# EC01_esquematico_easyeda.net
KiCad netlist of a schematic drawn in EasyEDA
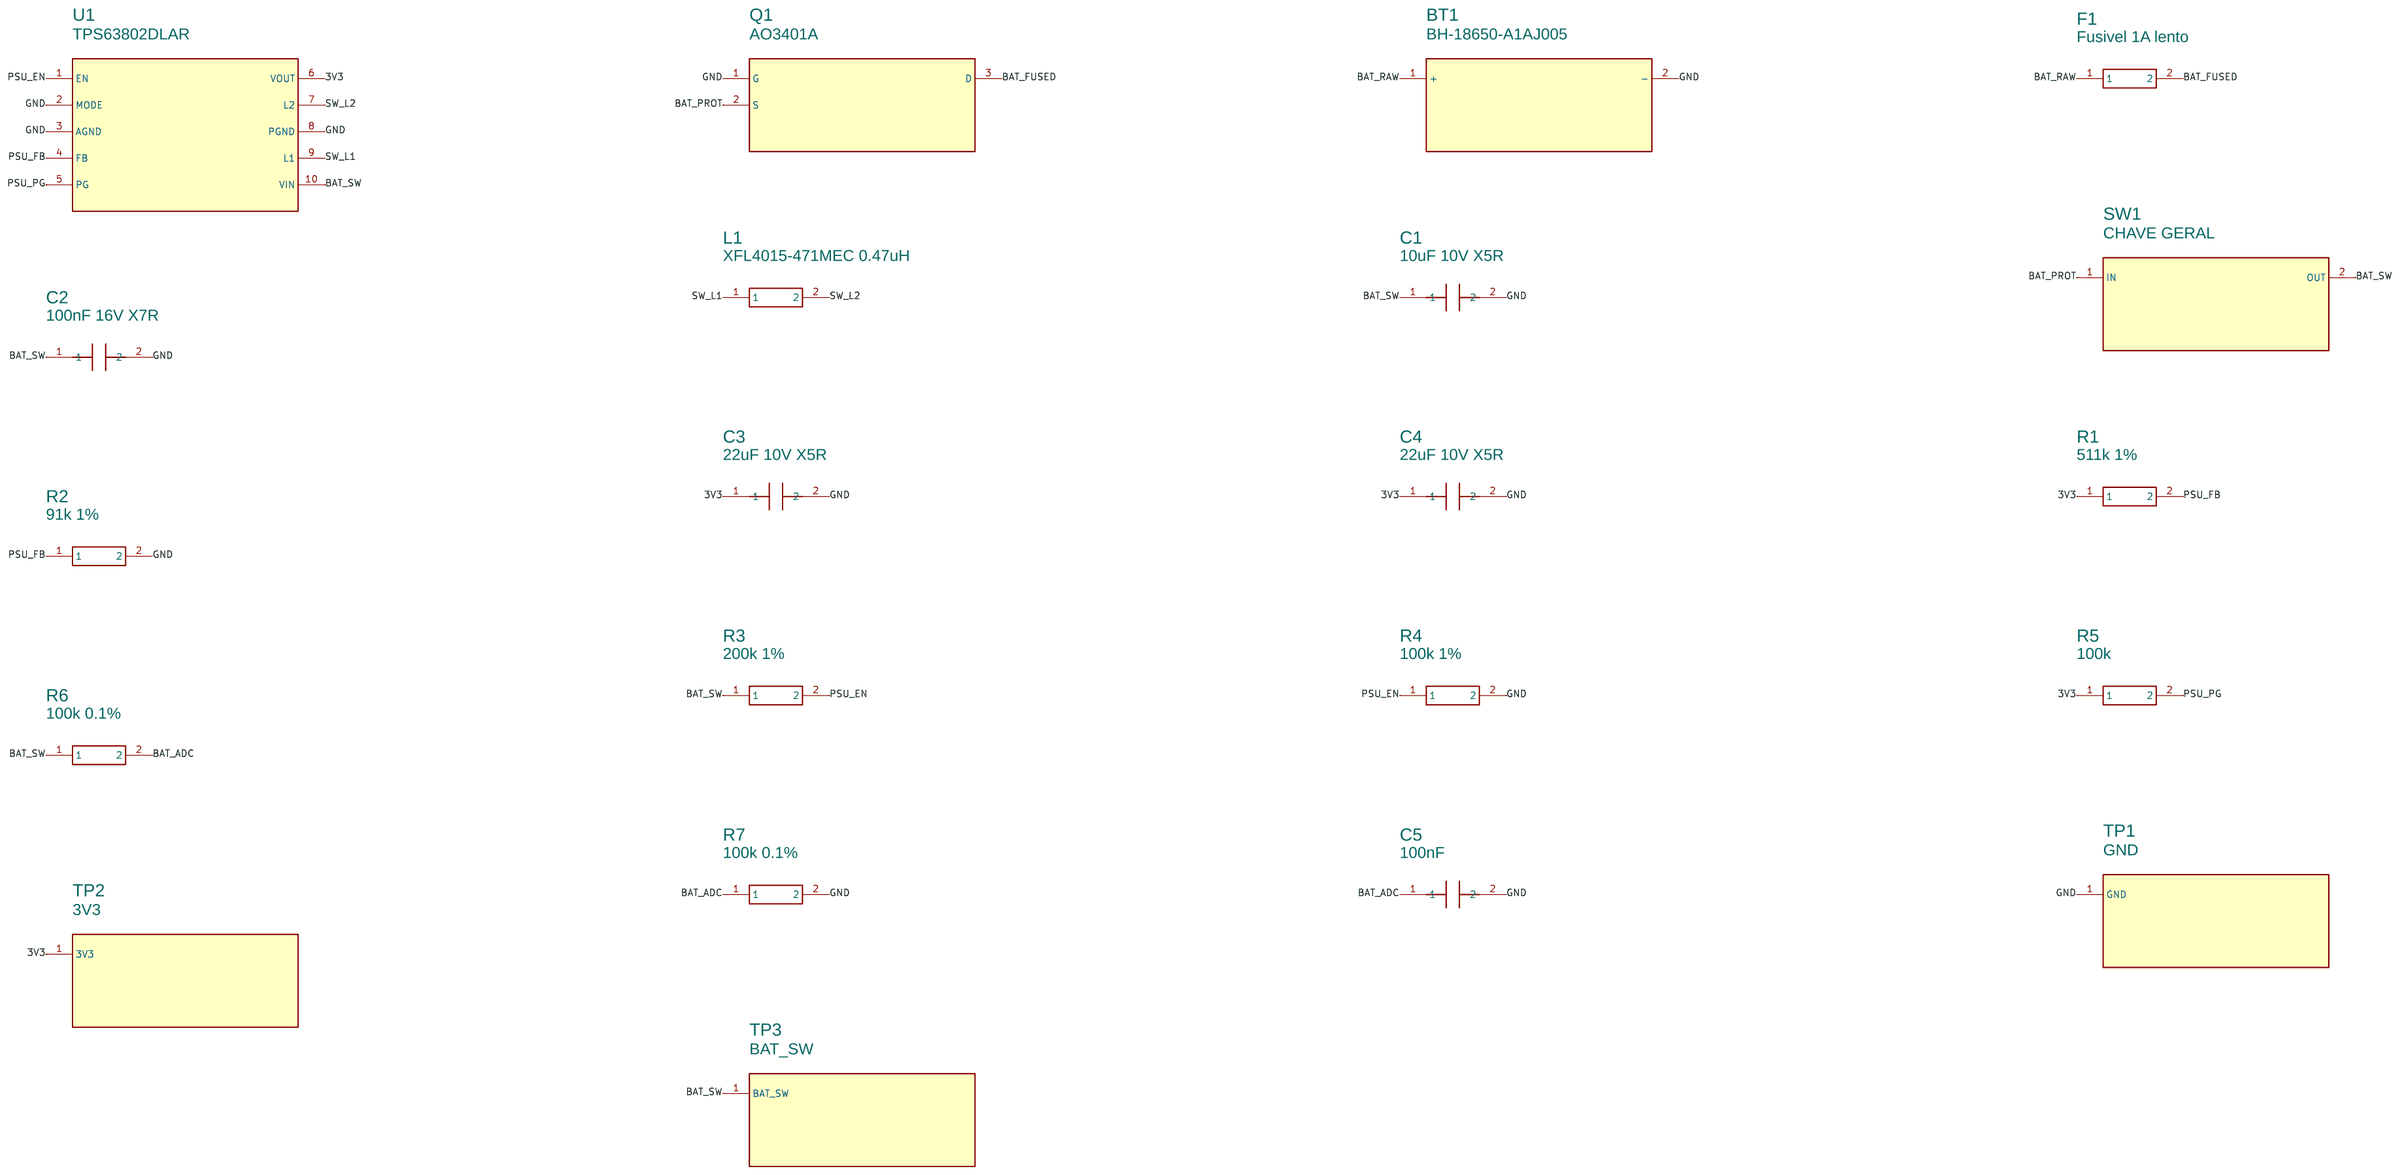
[diagram p0: 01 Alimentacao e bateria]
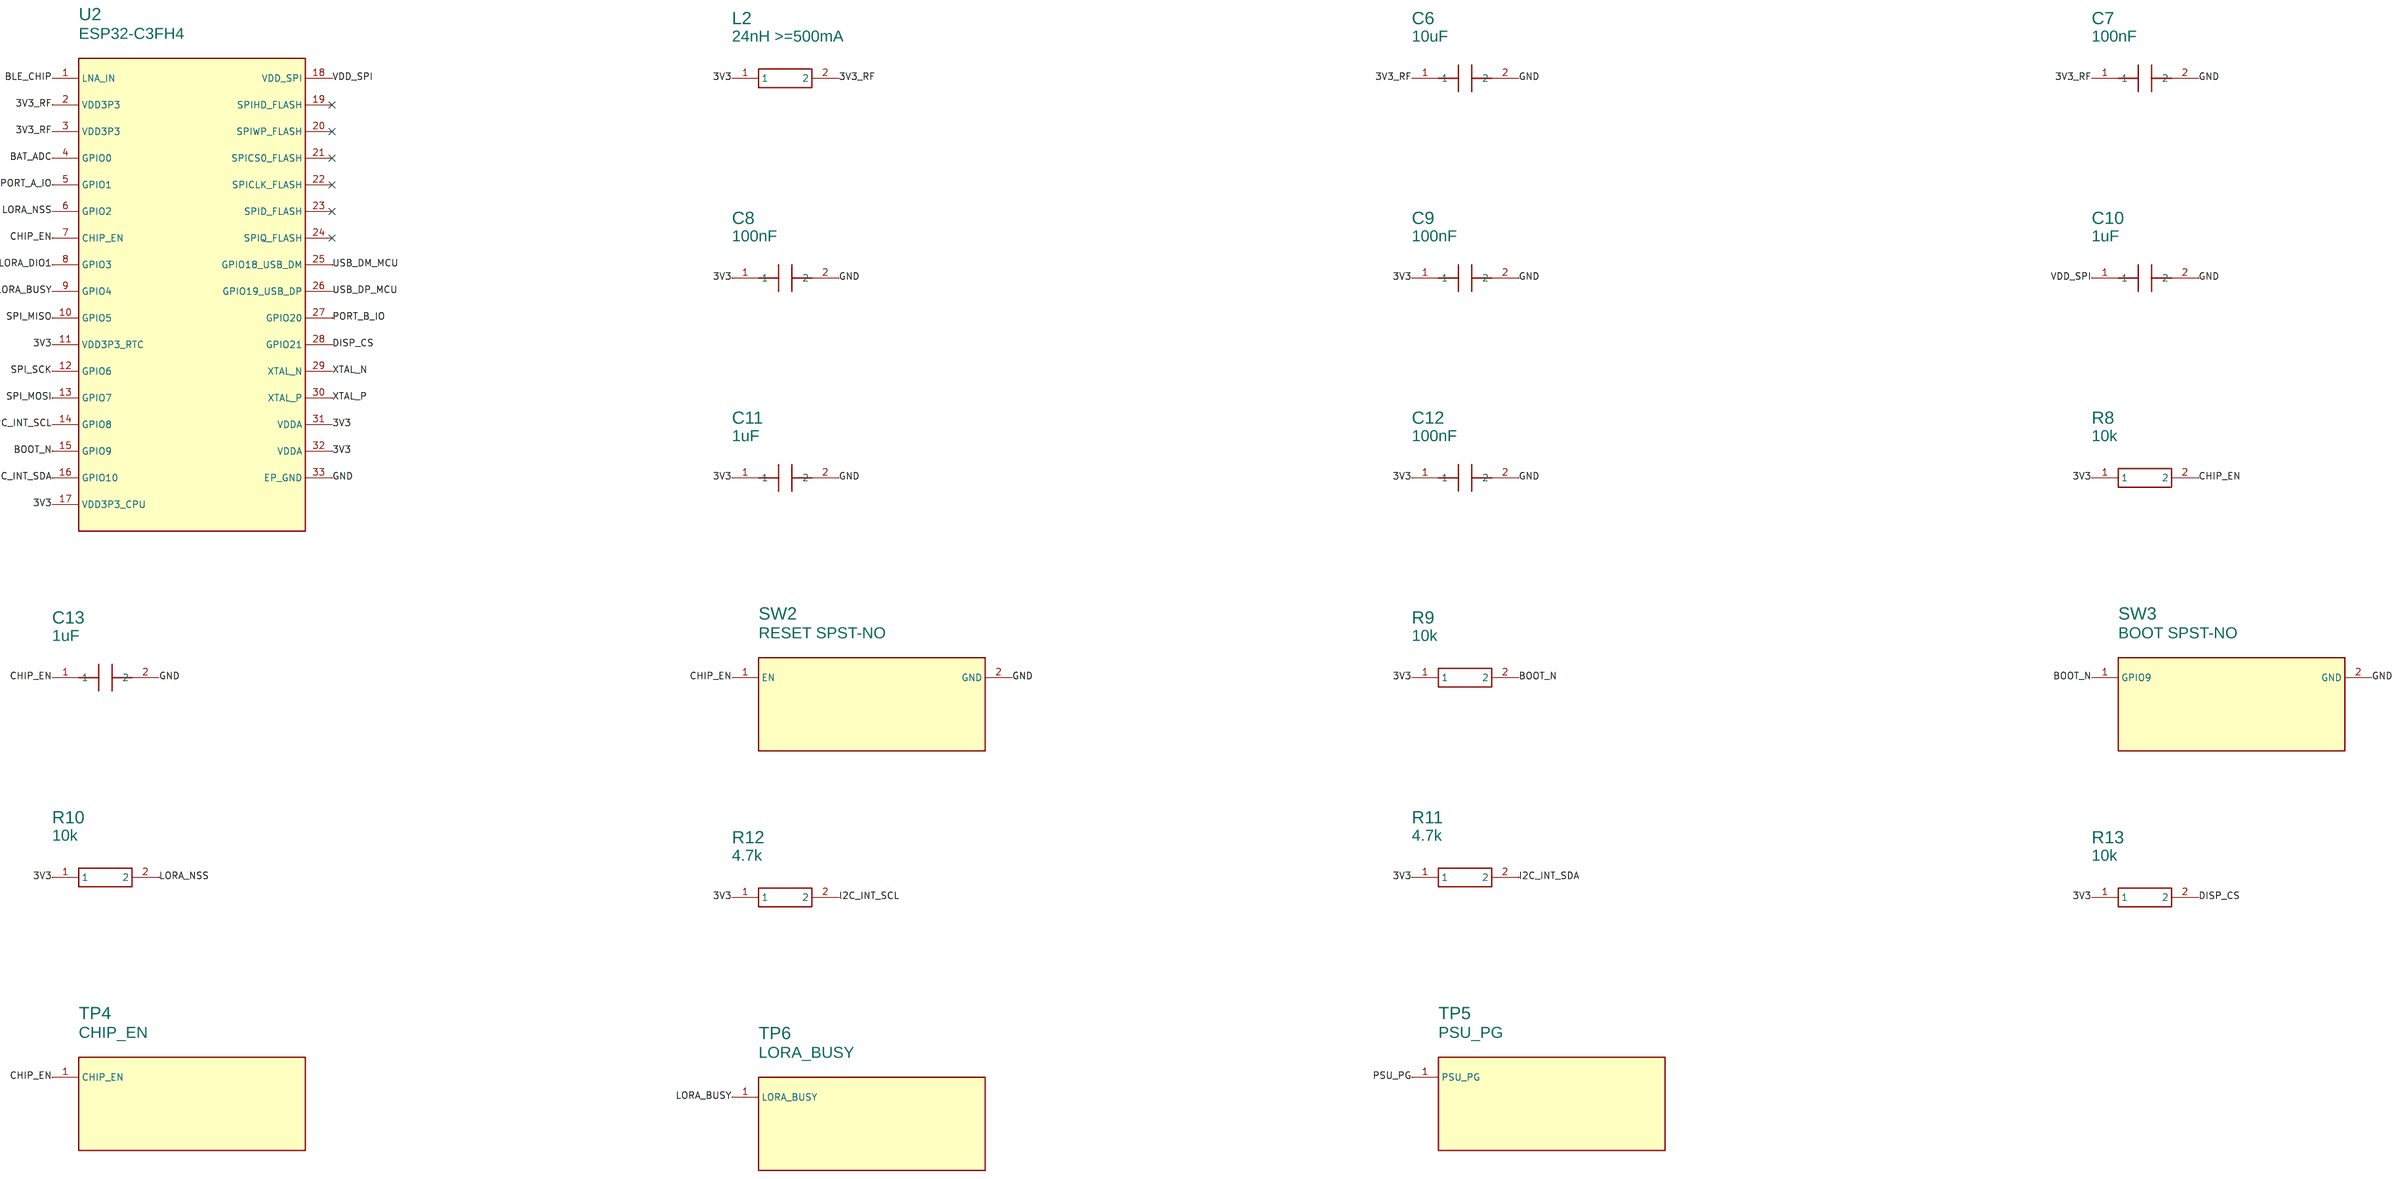
[diagram p1: 02 ESP32 e inicializacao]
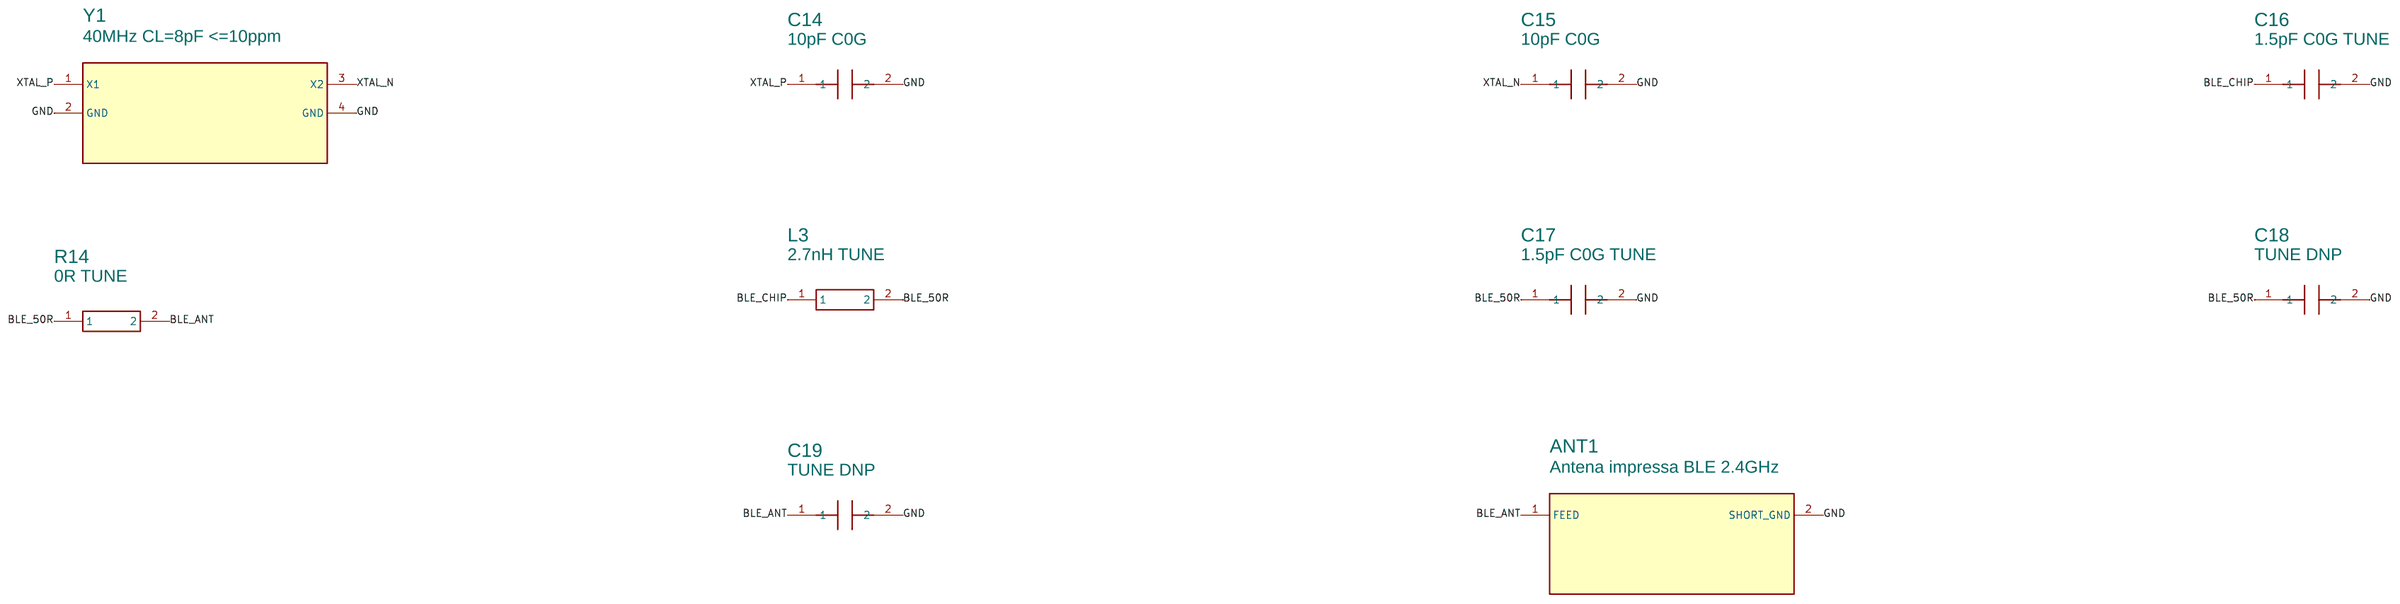
[diagram p2: 03 BLE e cristal]
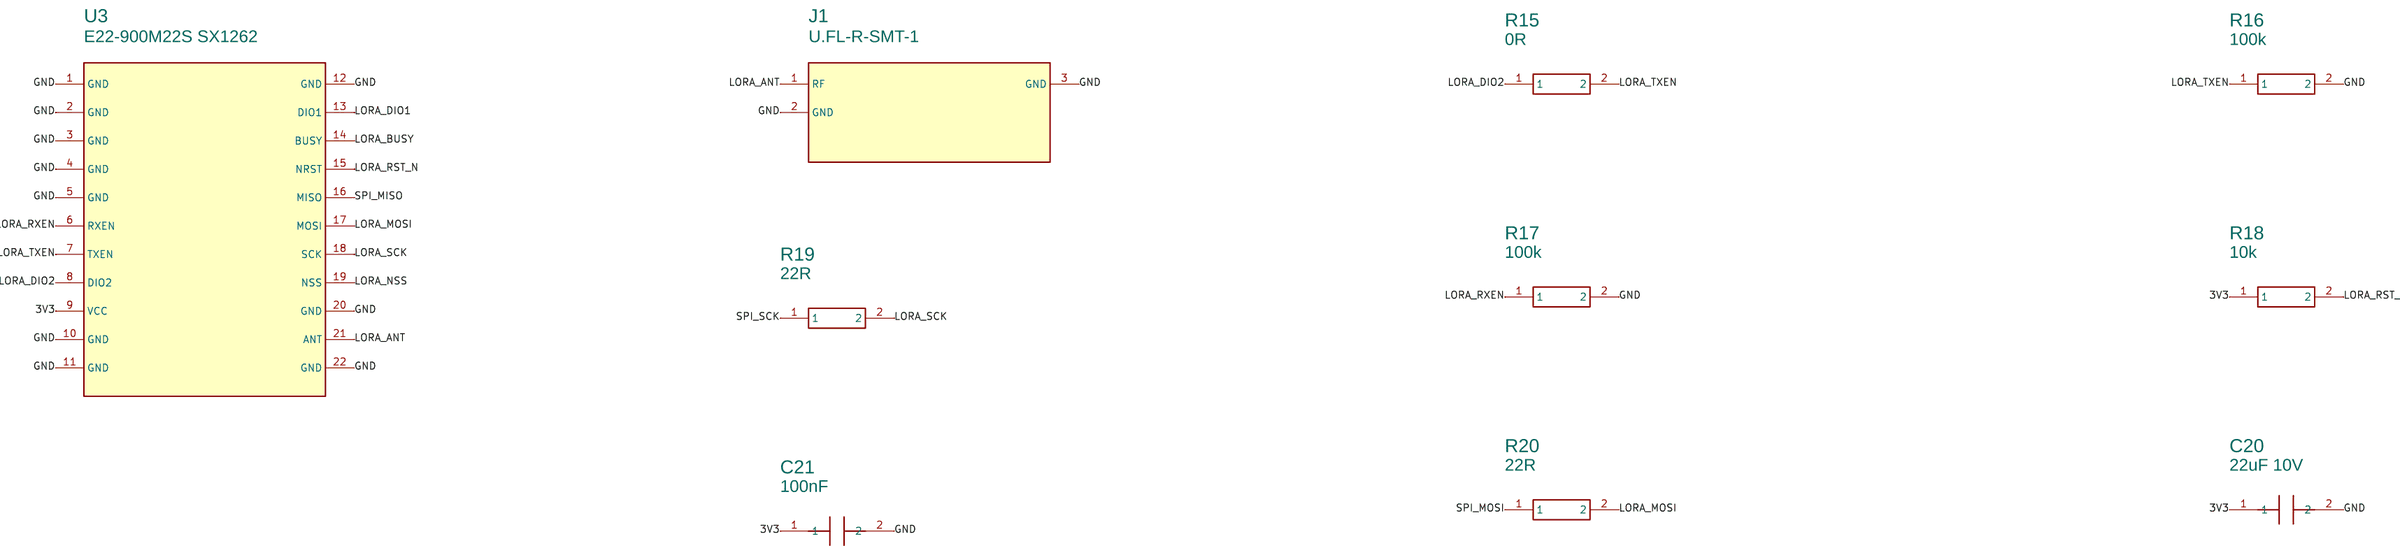
[diagram p3: 04 Radio LoRa]
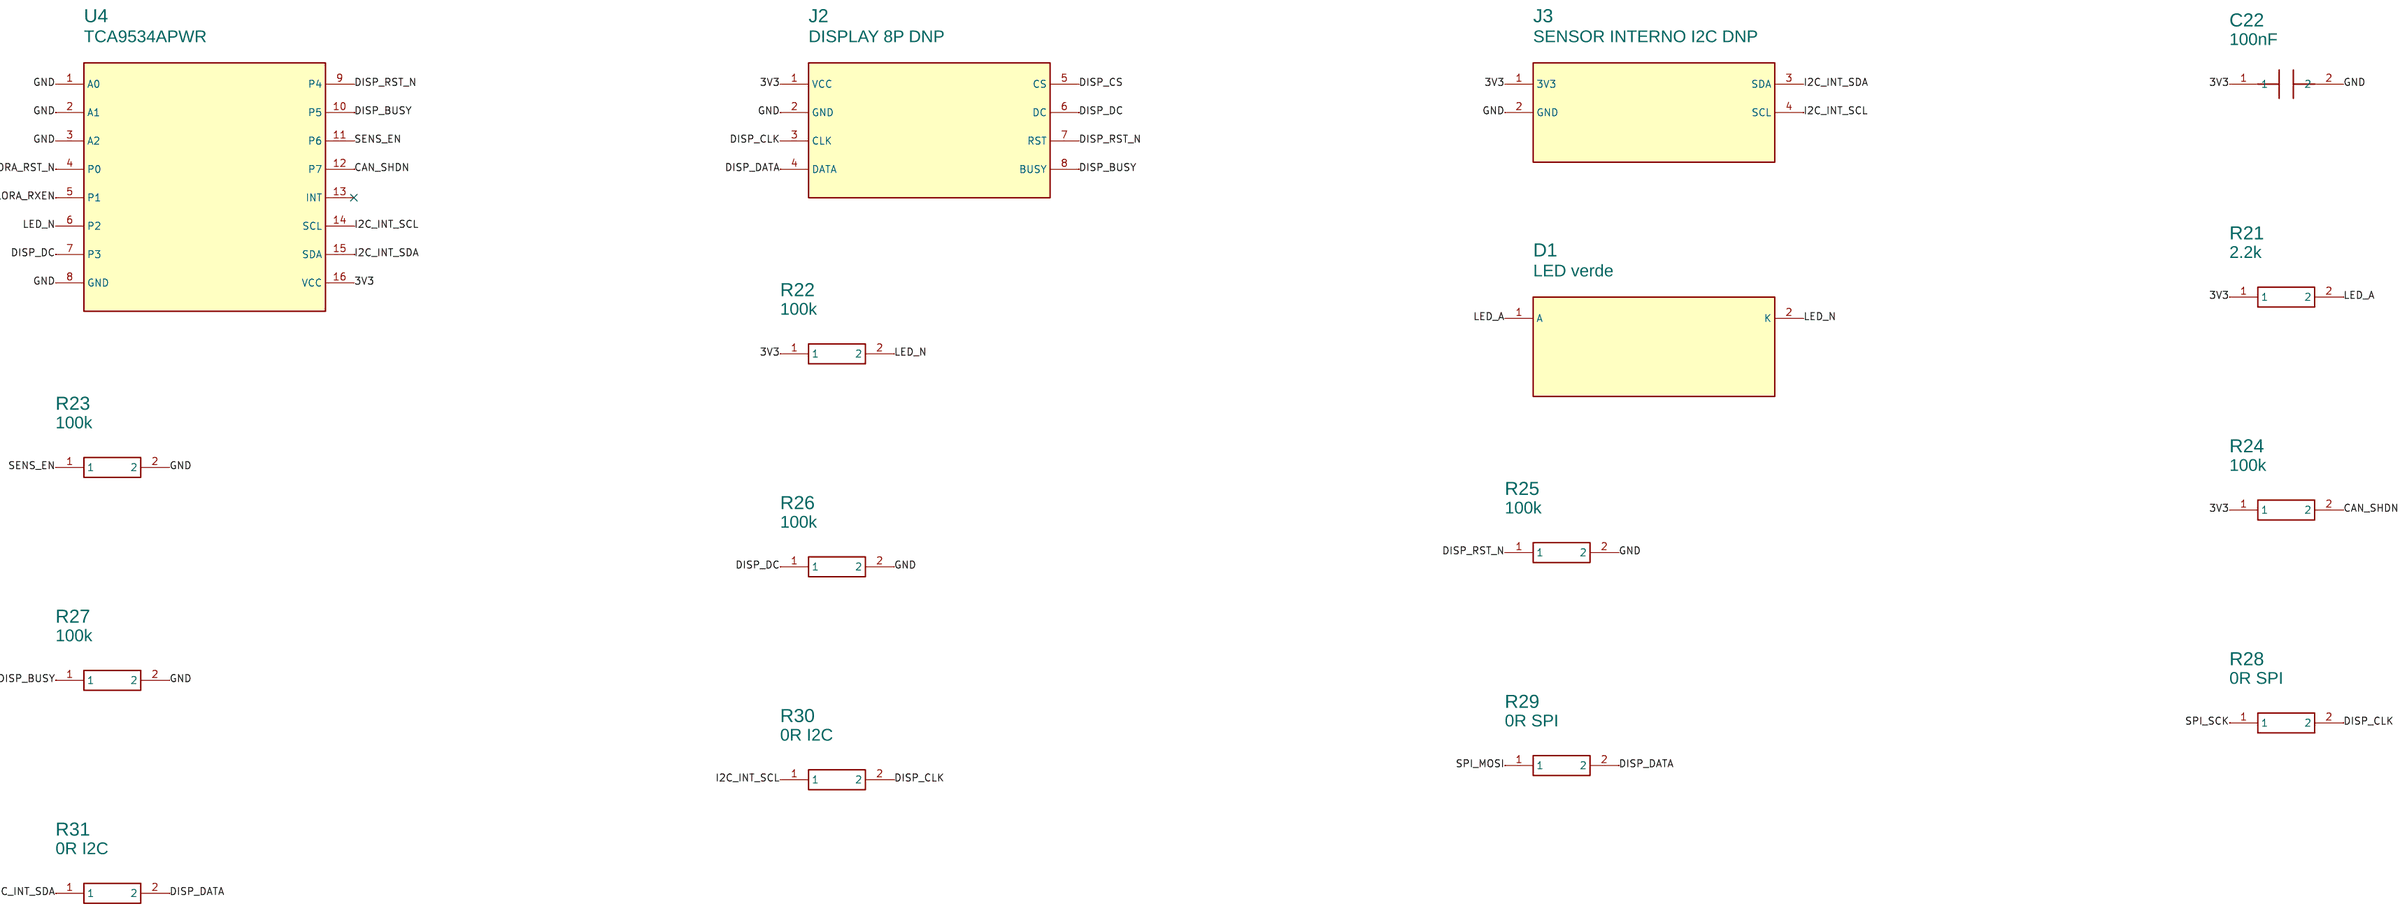
[diagram p4: 05 Expansao e display]
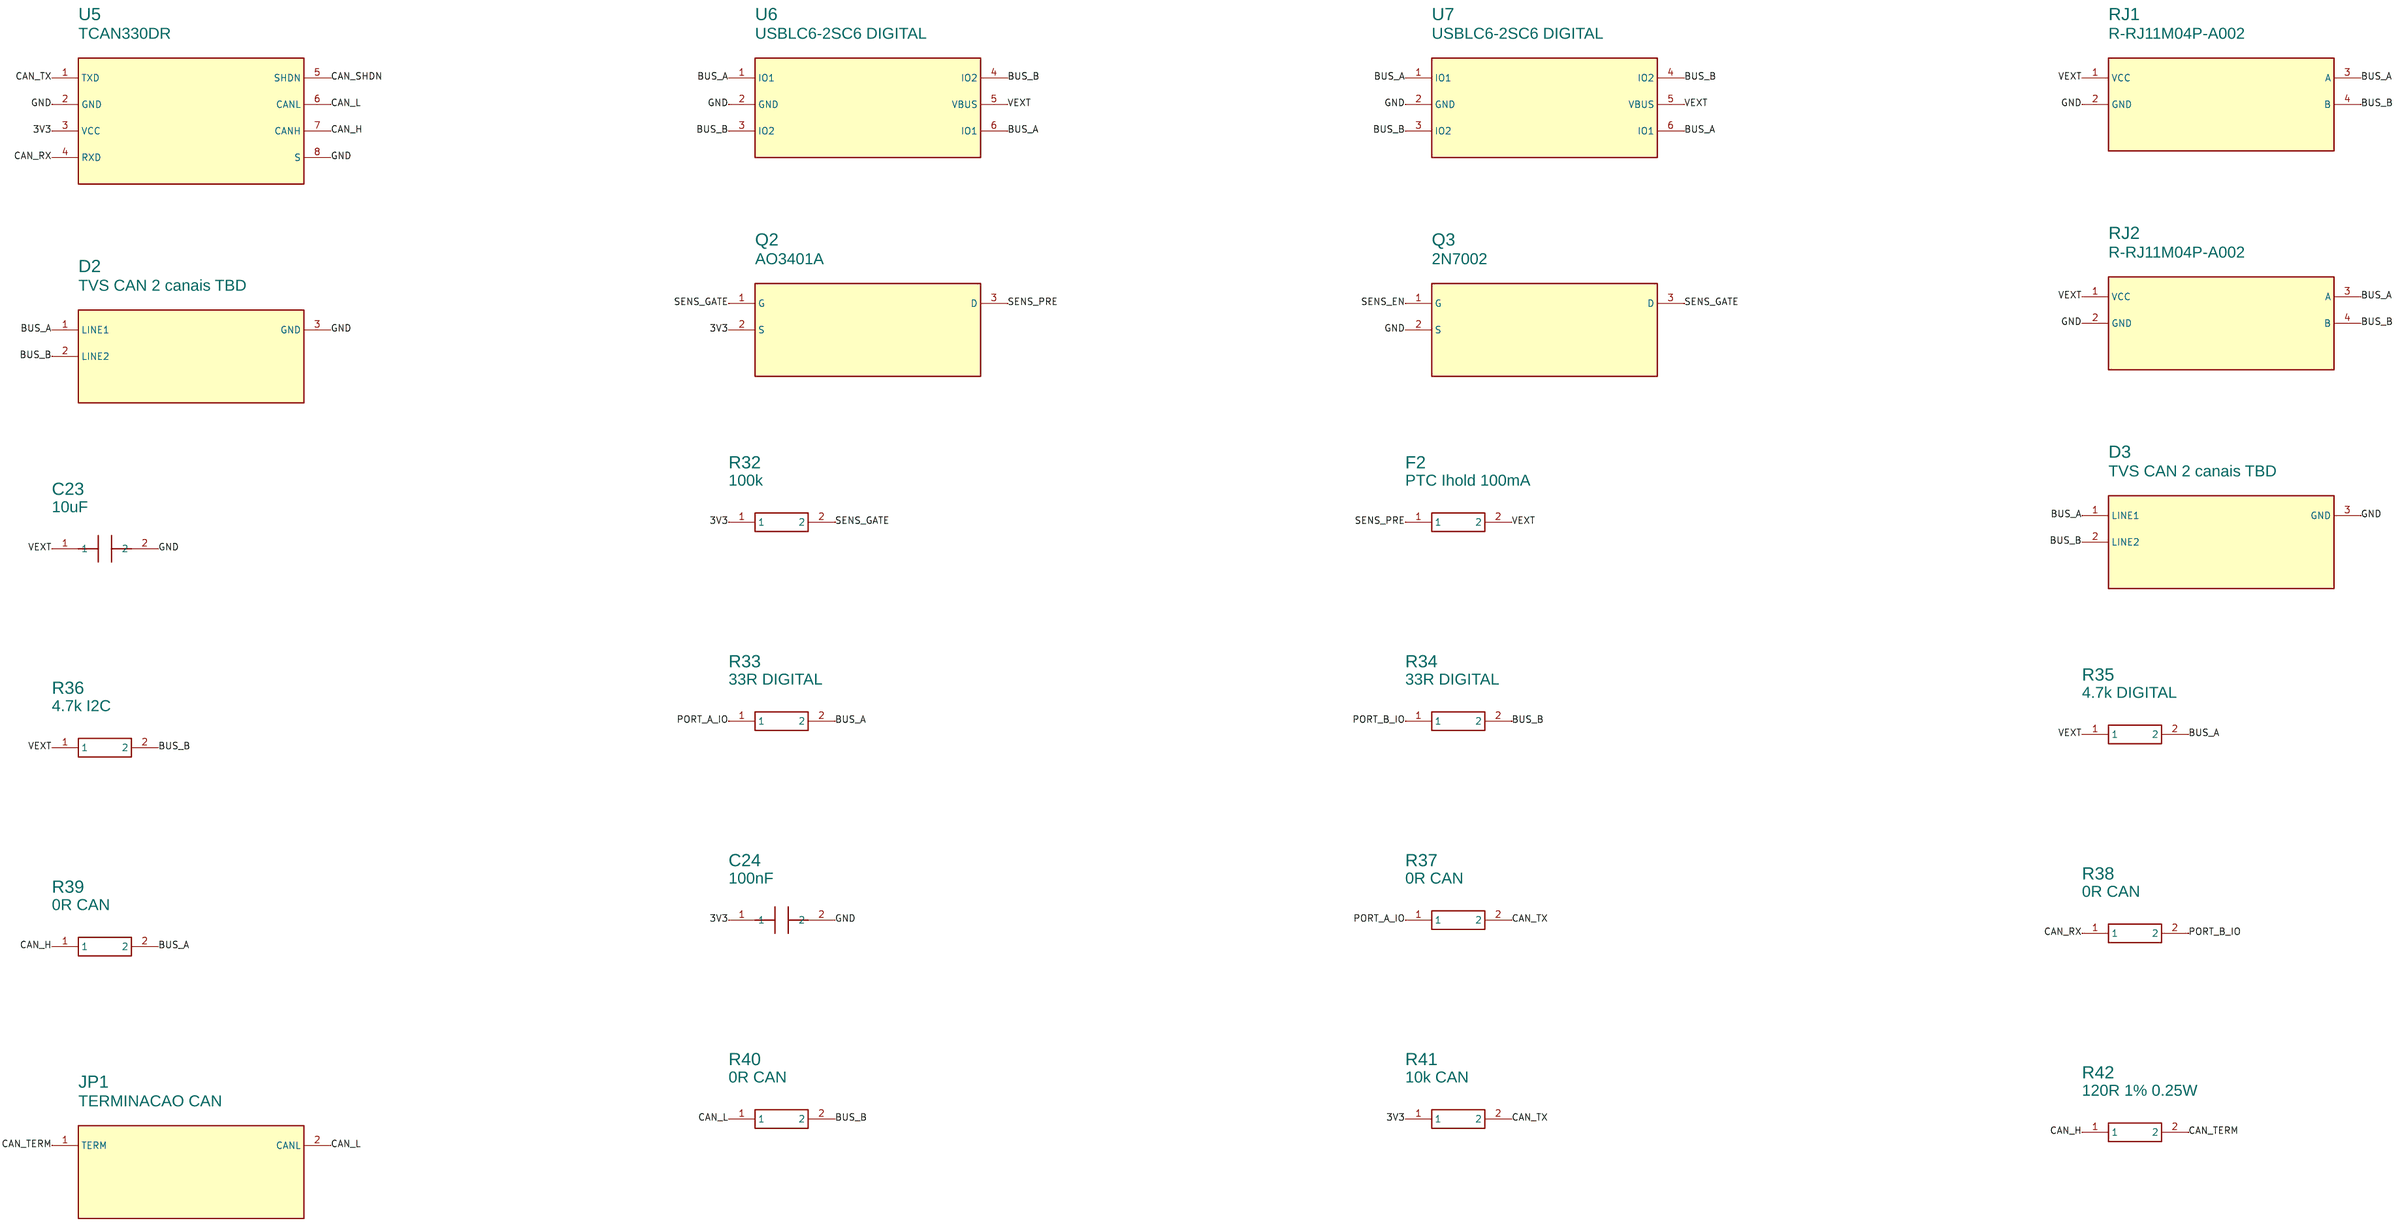
[diagram p5: 06 Sensores e CAN]
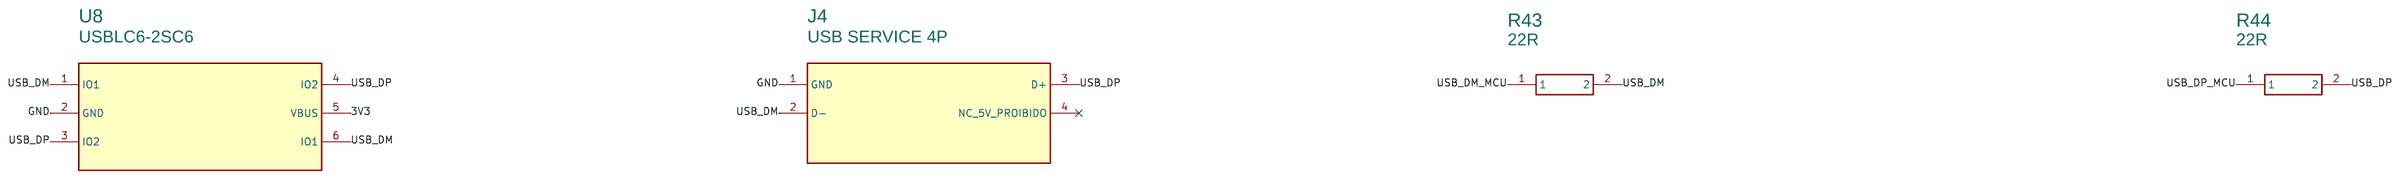
[diagram p6: 07 USB de servico]

(export (version "E")
  (design (tool "Eeschema 10.0.6"))
  (components
    (comp (ref "BT1") (value "BH-18650-A1AJ005") (libsource (lib "") (part "Unknown_1190_155")))
    (comp (ref "C1") (value "10uF 10V X5R") (libsource (lib "") (part "Unknown_1190_320")))
    (comp (ref "C2") (value "100nF 16V X7R") (libsource (lib "") (part "Unknown_170_365")))
    (comp (ref "C3") (value "22uF 10V X5R") (libsource (lib "") (part "Unknown_680_470")))
    (comp (ref "C4") (value "22uF 10V X5R") (libsource (lib "") (part "Unknown_1190_470")))
    (comp (ref "C5") (value "100nF") (libsource (lib "") (part "Unknown_1190_770")))
    (comp (ref "F1") (value "Fusivel 1A lento") (libsource (lib "") (part "Unknown_1700_155")))
    (comp (ref "L1") (value "XFL4015-471MEC 0.47uH") (libsource (lib "") (part "Unknown_680_320")))
    (comp (ref "Q1") (value "AO3401A") (libsource (lib "") (part "Unknown_680_155")))
    (comp (ref "R1") (value "511k 1%") (libsource (lib "") (part "Unknown_1700_470")))
    (comp (ref "R2") (value "91k 1%") (libsource (lib "") (part "Unknown_170_515")))
    (comp (ref "R3") (value "200k 1%") (libsource (lib "") (part "Unknown_680_620")))
    (comp (ref "R4") (value "100k 1%") (libsource (lib "") (part "Unknown_1190_620")))
    (comp (ref "R5") (value "100k") (libsource (lib "") (part "Unknown_1700_620")))
    (comp (ref "R6") (value "100k 0.1%") (libsource (lib "") (part "Unknown_170_665")))
    (comp (ref "R7") (value "100k 0.1%") (libsource (lib "") (part "Unknown_680_770")))
    (comp (ref "SW1") (value "CHAVE GERAL") (libsource (lib "") (part "Unknown_1700_305")))
    (comp (ref "TP1") (value "GND") (libsource (lib "") (part "Unknown_1700_770")))
    (comp (ref "TP2") (value "3V3") (libsource (lib "") (part "Unknown_170_815")))
    (comp (ref "TP3") (value "BAT_SW") (libsource (lib "") (part "Unknown_680_920")))
    (comp (ref "U1") (value "TPS63802DLAR") (libsource (lib "") (part "Unknown_170_155")))
    (comp (ref "C6") (value "10uF") (libsource (lib "") (part "Unknown_1190_155")))
    (comp (ref "C7") (value "100nF") (libsource (lib "") (part "Unknown_1700_155")))
    (comp (ref "C8") (value "100nF") (libsource (lib "") (part "Unknown_680_305")))
    (comp (ref "C9") (value "100nF") (libsource (lib "") (part "Unknown_1190_305")))
    (comp (ref "C10") (value "1uF") (libsource (lib "") (part "Unknown_1700_305")))
    (comp (ref "C11") (value "1uF") (libsource (lib "") (part "Unknown_680_455")))
    (comp (ref "C12") (value "100nF") (libsource (lib "") (part "Unknown_1190_455")))
    (comp (ref "C13") (value "1uF") (libsource (lib "") (part "Unknown_170_605")))
    (comp (ref "L2") (value "24nH >=500mA") (libsource (lib "") (part "Unknown_680_155")))
    (comp (ref "R8") (value "10k") (libsource (lib "") (part "Unknown_1700_455")))
    (comp (ref "R9") (value "10k") (libsource (lib "") (part "Unknown_1190_605")))
    (comp (ref "R10") (value "10k") (libsource (lib "") (part "Unknown_170_755")))
    (comp (ref "R11") (value "4.7k") (libsource (lib "") (part "Unknown_1190_755")))
    (comp (ref "R12") (value "4.7k") (libsource (lib "") (part "Unknown_680_770")))
    (comp (ref "R13") (value "10k") (libsource (lib "") (part "Unknown_1700_770")))
    (comp (ref "SW2") (value "RESET SPST-NO") (libsource (lib "") (part "Unknown_680_605")))
    (comp (ref "SW3") (value "BOOT SPST-NO") (libsource (lib "") (part "Unknown_1700_605")))
    (comp (ref "TP4") (value "CHIP_EN") (libsource (lib "") (part "Unknown_170_905")))
    (comp (ref "TP5") (value "PSU_PG") (libsource (lib "") (part "Unknown_1190_905")))
    (comp (ref "TP6") (value "LORA_BUSY") (libsource (lib "") (part "Unknown_680_920")))
    (comp (ref "U2") (value "ESP32-C3FH4") (libsource (lib "") (part "Unknown_170_155")))
    (comp (ref "ANT1") (value "Antena impressa BLE 2.4GHz") (libsource (lib "") (part "Unknown_1190_455")))
    (comp (ref "C14") (value "10pF C0G") (libsource (lib "") (part "Unknown_680_155")))
    (comp (ref "C15") (value "10pF C0G") (libsource (lib "") (part "Unknown_1190_155")))
    (comp (ref "C16") (value "1.5pF C0G TUNE") (libsource (lib "") (part "Unknown_1700_155")))
    (comp (ref "C17") (value "1.5pF C0G TUNE") (libsource (lib "") (part "Unknown_1190_305")))
    (comp (ref "C18") (value "TUNE DNP") (libsource (lib "") (part "Unknown_1700_305")))
    (comp (ref "C19") (value "TUNE DNP") (libsource (lib "") (part "Unknown_680_455")))
    (comp (ref "L3") (value "2.7nH TUNE") (libsource (lib "") (part "Unknown_680_305")))
    (comp (ref "R14") (value "0R TUNE") (libsource (lib "") (part "Unknown_170_320")))
    (comp (ref "Y1") (value "40MHz CL=8pF <=10ppm") (libsource (lib "") (part "Unknown_170_155")))
    (comp (ref "C20") (value "22uF 10V") (libsource (lib "") (part "Unknown_1700_455")))
    (comp (ref "C21") (value "100nF") (libsource (lib "") (part "Unknown_680_470")))
    (comp (ref "J1") (value "U.FL-R-SMT-1") (libsource (lib "") (part "Unknown_680_155")))
    (comp (ref "R15") (value "0R") (libsource (lib "") (part "Unknown_1190_155")))
    (comp (ref "R16") (value "100k") (libsource (lib "") (part "Unknown_1700_155")))
    (comp (ref "R17") (value "100k") (libsource (lib "") (part "Unknown_1190_305")))
    (comp (ref "R18") (value "10k") (libsource (lib "") (part "Unknown_1700_305")))
    (comp (ref "R19") (value "22R") (libsource (lib "") (part "Unknown_680_320")))
    (comp (ref "R20") (value "22R") (libsource (lib "") (part "Unknown_1190_455")))
    (comp (ref "U3") (value "E22-900M22S SX1262") (libsource (lib "") (part "Unknown_170_155")))
    (comp (ref "C22") (value "100nF") (libsource (lib "") (part "Unknown_1700_155")))
    (comp (ref "D1") (value "LED verde") (libsource (lib "") (part "Unknown_1190_320")))
    (comp (ref "J2") (value "DISPLAY 8P DNP") (libsource (lib "") (part "Unknown_680_155")))
    (comp (ref "J3") (value "SENSOR INTERNO I2C DNP") (libsource (lib "") (part "Unknown_1190_155")))
    (comp (ref "R21") (value "2.2k") (libsource (lib "") (part "Unknown_1700_305")))
    (comp (ref "R22") (value "100k") (libsource (lib "") (part "Unknown_680_345")))
    (comp (ref "R23") (value "100k") (libsource (lib "") (part "Unknown_170_425")))
    (comp (ref "R24") (value "100k") (libsource (lib "") (part "Unknown_1700_455")))
    (comp (ref "R25") (value "100k") (libsource (lib "") (part "Unknown_1190_485")))
    (comp (ref "R26") (value "100k") (libsource (lib "") (part "Unknown_680_495")))
    (comp (ref "R27") (value "100k") (libsource (lib "") (part "Unknown_170_575")))
    (comp (ref "R28") (value "0R SPI") (libsource (lib "") (part "Unknown_1700_605")))
    (comp (ref "R29") (value "0R SPI") (libsource (lib "") (part "Unknown_1190_635")))
    (comp (ref "R30") (value "0R I2C") (libsource (lib "") (part "Unknown_680_645")))
    (comp (ref "R31") (value "0R I2C") (libsource (lib "") (part "Unknown_170_725")))
    (comp (ref "U4") (value "TCA9534APWR") (libsource (lib "") (part "Unknown_170_155")))
    (comp (ref "C23") (value "10uF") (libsource (lib "") (part "Unknown_170_510")))
    (comp (ref "C24") (value "100nF") (libsource (lib "") (part "Unknown_680_790")))
    (comp (ref "D2") (value "TVS CAN 2 canais TBD") (libsource (lib "") (part "Unknown_170_345")))
    (comp (ref "D3") (value "TVS CAN 2 canais TBD") (libsource (lib "") (part "Unknown_1700_485")))
    (comp (ref "F2") (value "PTC Ihold 100mA") (libsource (lib "") (part "Unknown_1190_490")))
    (comp (ref "JP1") (value "TERMINACAO CAN") (libsource (lib "") (part "Unknown_170_960")))
    (comp (ref "Q2") (value "AO3401A") (libsource (lib "") (part "Unknown_680_325")))
    (comp (ref "Q3") (value "2N7002") (libsource (lib "") (part "Unknown_1190_325")))
    (comp (ref "R32") (value "100k") (libsource (lib "") (part "Unknown_680_490")))
    (comp (ref "R33") (value "33R DIGITAL") (libsource (lib "") (part "Unknown_680_640")))
    (comp (ref "R34") (value "33R DIGITAL") (libsource (lib "") (part "Unknown_1190_640")))
    (comp (ref "R35") (value "4.7k DIGITAL") (libsource (lib "") (part "Unknown_1700_650")))
    (comp (ref "R36") (value "4.7k I2C") (libsource (lib "") (part "Unknown_170_660")))
    (comp (ref "R37") (value "0R CAN") (libsource (lib "") (part "Unknown_1190_790")))
    (comp (ref "R38") (value "0R CAN") (libsource (lib "") (part "Unknown_1700_800")))
    (comp (ref "R39") (value "0R CAN") (libsource (lib "") (part "Unknown_170_810")))
    (comp (ref "R40") (value "0R CAN") (libsource (lib "") (part "Unknown_680_940")))
    (comp (ref "R41") (value "10k CAN") (libsource (lib "") (part "Unknown_1190_940")))
    (comp (ref "R42") (value "120R 1% 0.25W") (libsource (lib "") (part "Unknown_1700_950")))
    (comp (ref "RJ1") (value "R-RJ11M04P-A002") (libsource (lib "") (part "Unknown_1700_155")))
    (comp (ref "RJ2") (value "R-RJ11M04P-A002") (libsource (lib "") (part "Unknown_1700_320")))
    (comp (ref "U5") (value "TCAN330DR") (libsource (lib "") (part "Unknown_170_155")))
    (comp (ref "U6") (value "USBLC6-2SC6 DIGITAL") (libsource (lib "") (part "Unknown_680_155")))
    (comp (ref "U7") (value "USBLC6-2SC6 DIGITAL") (libsource (lib "") (part "Unknown_1190_155")))
    (comp (ref "J4") (value "USB SERVICE 4P") (libsource (lib "") (part "Unknown_680_155")))
    (comp (ref "R43") (value "22R") (libsource (lib "") (part "Unknown_1190_155")))
    (comp (ref "R44") (value "22R") (libsource (lib "") (part "Unknown_1700_155")))
    (comp (ref "U8") (value "USBLC6-2SC6") (libsource (lib "") (part "Unknown_170_155")))
  )
  (nets
    (net (code "1") (name "3V3") (class "Default")
      (node (ref "C11") (pin "1") (pinfunction "1_1") (pintype "unspecified"))
      (node (ref "C12") (pin "1") (pinfunction "1_1") (pintype "unspecified"))
      (node (ref "C20") (pin "1") (pinfunction "1_1") (pintype "unspecified"))
      (node (ref "C21") (pin "1") (pinfunction "1_1") (pintype "unspecified"))
      (node (ref "C22") (pin "1") (pinfunction "1_1") (pintype "unspecified"))
      (node (ref "C24") (pin "1") (pinfunction "1_1") (pintype "unspecified"))
      (node (ref "C3") (pin "1") (pinfunction "1_1") (pintype "unspecified"))
      (node (ref "C4") (pin "1") (pinfunction "1_1") (pintype "unspecified"))
      (node (ref "C8") (pin "1") (pinfunction "1_1") (pintype "unspecified"))
      (node (ref "C9") (pin "1") (pinfunction "1_1") (pintype "unspecified"))
      (node (ref "J2") (pin "1") (pinfunction "VCC_1") (pintype "unspecified"))
      (node (ref "J3") (pin "1") (pinfunction "3V3_1") (pintype "unspecified"))
      (node (ref "L2") (pin "1") (pinfunction "1_1") (pintype "unspecified"))
      (node (ref "Q2") (pin "2") (pinfunction "S_2") (pintype "unspecified"))
      (node (ref "R1") (pin "1") (pinfunction "1_1") (pintype "unspecified"))
      (node (ref "R10") (pin "1") (pinfunction "1_1") (pintype "unspecified"))
      (node (ref "R11") (pin "1") (pinfunction "1_1") (pintype "unspecified"))
      (node (ref "R12") (pin "1") (pinfunction "1_1") (pintype "unspecified"))
      (node (ref "R13") (pin "1") (pinfunction "1_1") (pintype "unspecified"))
      (node (ref "R18") (pin "1") (pinfunction "1_1") (pintype "unspecified"))
      (node (ref "R21") (pin "1") (pinfunction "1_1") (pintype "unspecified"))
      (node (ref "R22") (pin "1") (pinfunction "1_1") (pintype "unspecified"))
      (node (ref "R24") (pin "1") (pinfunction "1_1") (pintype "unspecified"))
      (node (ref "R32") (pin "1") (pinfunction "1_1") (pintype "unspecified"))
      (node (ref "R41") (pin "1") (pinfunction "1_1") (pintype "unspecified"))
      (node (ref "R5") (pin "1") (pinfunction "1_1") (pintype "unspecified"))
      (node (ref "R8") (pin "1") (pinfunction "1_1") (pintype "unspecified"))
      (node (ref "R9") (pin "1") (pinfunction "1_1") (pintype "unspecified"))
      (node (ref "TP2") (pin "1") (pinfunction "3V3_1") (pintype "unspecified"))
      (node (ref "U1") (pin "6") (pinfunction "VOUT_6") (pintype "unspecified"))
      (node (ref "U2") (pin "11") (pinfunction "VDD3P3_RTC_11") (pintype "unspecified"))
      (node (ref "U2") (pin "17") (pinfunction "VDD3P3_CPU_17") (pintype "unspecified"))
      (node (ref "U2") (pin "31") (pinfunction "VDDA_31") (pintype "unspecified"))
      (node (ref "U2") (pin "32") (pinfunction "VDDA_32") (pintype "unspecified"))
      (node (ref "U3") (pin "9") (pinfunction "VCC_9") (pintype "unspecified"))
      (node (ref "U4") (pin "16") (pinfunction "VCC_16") (pintype "unspecified"))
      (node (ref "U5") (pin "3") (pinfunction "VCC_3") (pintype "unspecified"))
      (node (ref "U8") (pin "5") (pinfunction "VBUS_5") (pintype "unspecified"))
    )
    (net (code "2") (name "3V3_RF") (class "Default")
      (node (ref "C6") (pin "1") (pinfunction "1_1") (pintype "unspecified"))
      (node (ref "C7") (pin "1") (pinfunction "1_1") (pintype "unspecified"))
      (node (ref "L2") (pin "2") (pinfunction "2_2") (pintype "unspecified"))
      (node (ref "U2") (pin "2") (pinfunction "VDD3P3_2") (pintype "unspecified"))
      (node (ref "U2") (pin "3") (pinfunction "VDD3P3_3") (pintype "unspecified"))
    )
    (net (code "3") (name "BAT_ADC") (class "Default")
      (node (ref "C5") (pin "1") (pinfunction "1_1") (pintype "unspecified"))
      (node (ref "R6") (pin "2") (pinfunction "2_2") (pintype "unspecified"))
      (node (ref "R7") (pin "1") (pinfunction "1_1") (pintype "unspecified"))
      (node (ref "U2") (pin "4") (pinfunction "GPIO0_4") (pintype "unspecified"))
    )
    (net (code "4") (name "BAT_FUSED") (class "Default")
      (node (ref "F1") (pin "2") (pinfunction "2_2") (pintype "unspecified"))
      (node (ref "Q1") (pin "3") (pinfunction "D_3") (pintype "unspecified"))
    )
    (net (code "5") (name "BAT_PROT") (class "Default")
      (node (ref "Q1") (pin "2") (pinfunction "S_2") (pintype "unspecified"))
      (node (ref "SW1") (pin "1") (pinfunction "IN_1") (pintype "unspecified"))
    )
    (net (code "6") (name "BAT_RAW") (class "Default")
      (node (ref "BT1") (pin "1") (pinfunction "+_1") (pintype "unspecified"))
      (node (ref "F1") (pin "1") (pinfunction "1_1") (pintype "unspecified"))
    )
    (net (code "7") (name "BAT_SW") (class "Default")
      (node (ref "C1") (pin "1") (pinfunction "1_1") (pintype "unspecified"))
      (node (ref "C2") (pin "1") (pinfunction "1_1") (pintype "unspecified"))
      (node (ref "R3") (pin "1") (pinfunction "1_1") (pintype "unspecified"))
      (node (ref "R6") (pin "1") (pinfunction "1_1") (pintype "unspecified"))
      (node (ref "SW1") (pin "2") (pinfunction "OUT_2") (pintype "unspecified"))
      (node (ref "TP3") (pin "1") (pinfunction "BAT_SW_1") (pintype "unspecified"))
      (node (ref "U1") (pin "10") (pinfunction "VIN_10") (pintype "unspecified"))
    )
    (net (code "8") (name "BLE_50R") (class "Default")
      (node (ref "C17") (pin "1") (pinfunction "1_1") (pintype "unspecified"))
      (node (ref "C18") (pin "1") (pinfunction "1_1") (pintype "unspecified"))
      (node (ref "L3") (pin "2") (pinfunction "2_2") (pintype "unspecified"))
      (node (ref "R14") (pin "1") (pinfunction "1_1") (pintype "unspecified"))
    )
    (net (code "9") (name "BLE_ANT") (class "Default")
      (node (ref "ANT1") (pin "1") (pinfunction "FEED_1") (pintype "unspecified"))
      (node (ref "C19") (pin "1") (pinfunction "1_1") (pintype "unspecified"))
      (node (ref "R14") (pin "2") (pinfunction "2_2") (pintype "unspecified"))
    )
    (net (code "10") (name "BLE_CHIP") (class "Default")
      (node (ref "C16") (pin "1") (pinfunction "1_1") (pintype "unspecified"))
      (node (ref "L3") (pin "1") (pinfunction "1_1") (pintype "unspecified"))
      (node (ref "U2") (pin "1") (pinfunction "LNA_IN_1") (pintype "unspecified"))
    )
    (net (code "11") (name "BOOT_N") (class "Default")
      (node (ref "R9") (pin "2") (pinfunction "2_2") (pintype "unspecified"))
      (node (ref "SW3") (pin "1") (pinfunction "GPIO9_1") (pintype "unspecified"))
      (node (ref "U2") (pin "15") (pinfunction "GPIO9_15") (pintype "unspecified"))
    )
    (net (code "12") (name "BUS_A") (class "Default")
      (node (ref "D2") (pin "1") (pinfunction "LINE1_1") (pintype "unspecified"))
      (node (ref "D3") (pin "1") (pinfunction "LINE1_1") (pintype "unspecified"))
      (node (ref "R33") (pin "2") (pinfunction "2_2") (pintype "unspecified"))
      (node (ref "R35") (pin "2") (pinfunction "2_2") (pintype "unspecified"))
      (node (ref "R39") (pin "2") (pinfunction "2_2") (pintype "unspecified"))
      (node (ref "RJ1") (pin "3") (pinfunction "A_3") (pintype "unspecified"))
      (node (ref "RJ2") (pin "3") (pinfunction "A_3") (pintype "unspecified"))
      (node (ref "U6") (pin "1") (pinfunction "IO1_1") (pintype "unspecified"))
      (node (ref "U6") (pin "6") (pinfunction "IO1_6") (pintype "unspecified"))
      (node (ref "U7") (pin "1") (pinfunction "IO1_1") (pintype "unspecified"))
      (node (ref "U7") (pin "6") (pinfunction "IO1_6") (pintype "unspecified"))
    )
    (net (code "13") (name "BUS_B") (class "Default")
      (node (ref "D2") (pin "2") (pinfunction "LINE2_2") (pintype "unspecified"))
      (node (ref "D3") (pin "2") (pinfunction "LINE2_2") (pintype "unspecified"))
      (node (ref "R34") (pin "2") (pinfunction "2_2") (pintype "unspecified"))
      (node (ref "R36") (pin "2") (pinfunction "2_2") (pintype "unspecified"))
      (node (ref "R40") (pin "2") (pinfunction "2_2") (pintype "unspecified"))
      (node (ref "RJ1") (pin "4") (pinfunction "B_4") (pintype "unspecified"))
      (node (ref "RJ2") (pin "4") (pinfunction "B_4") (pintype "unspecified"))
      (node (ref "U6") (pin "3") (pinfunction "IO2_3") (pintype "unspecified"))
      (node (ref "U6") (pin "4") (pinfunction "IO2_4") (pintype "unspecified"))
      (node (ref "U7") (pin "3") (pinfunction "IO2_3") (pintype "unspecified"))
      (node (ref "U7") (pin "4") (pinfunction "IO2_4") (pintype "unspecified"))
    )
    (net (code "14") (name "CAN_H") (class "Default")
      (node (ref "R39") (pin "1") (pinfunction "1_1") (pintype "unspecified"))
      (node (ref "R42") (pin "1") (pinfunction "1_1") (pintype "unspecified"))
      (node (ref "U5") (pin "7") (pinfunction "CANH_7") (pintype "unspecified"))
    )
    (net (code "15") (name "CAN_L") (class "Default")
      (node (ref "JP1") (pin "2") (pinfunction "CANL_2") (pintype "unspecified"))
      (node (ref "R40") (pin "1") (pinfunction "1_1") (pintype "unspecified"))
      (node (ref "U5") (pin "6") (pinfunction "CANL_6") (pintype "unspecified"))
    )
    (net (code "16") (name "CAN_RX") (class "Default")
      (node (ref "R38") (pin "1") (pinfunction "1_1") (pintype "unspecified"))
      (node (ref "U5") (pin "4") (pinfunction "RXD_4") (pintype "unspecified"))
    )
    (net (code "17") (name "CAN_SHDN") (class "Default")
      (node (ref "R24") (pin "2") (pinfunction "2_2") (pintype "unspecified"))
      (node (ref "U4") (pin "12") (pinfunction "P7_12") (pintype "unspecified"))
      (node (ref "U5") (pin "5") (pinfunction "SHDN_5") (pintype "unspecified"))
    )
    (net (code "18") (name "CAN_TERM") (class "Default")
      (node (ref "JP1") (pin "1") (pinfunction "TERM_1") (pintype "unspecified"))
      (node (ref "R42") (pin "2") (pinfunction "2_2") (pintype "unspecified"))
    )
    (net (code "19") (name "CAN_TX") (class "Default")
      (node (ref "R37") (pin "2") (pinfunction "2_2") (pintype "unspecified"))
      (node (ref "R41") (pin "2") (pinfunction "2_2") (pintype "unspecified"))
      (node (ref "U5") (pin "1") (pinfunction "TXD_1") (pintype "unspecified"))
    )
    (net (code "20") (name "CHIP_EN") (class "Default")
      (node (ref "C13") (pin "1") (pinfunction "1_1") (pintype "unspecified"))
      (node (ref "R8") (pin "2") (pinfunction "2_2") (pintype "unspecified"))
      (node (ref "SW2") (pin "1") (pinfunction "EN_1") (pintype "unspecified"))
      (node (ref "TP4") (pin "1") (pinfunction "CHIP_EN_1") (pintype "unspecified"))
      (node (ref "U2") (pin "7") (pinfunction "CHIP_EN_7") (pintype "unspecified"))
    )
    (net (code "21") (name "DISP_BUSY") (class "Default")
      (node (ref "J2") (pin "8") (pinfunction "BUSY_8") (pintype "unspecified"))
      (node (ref "R27") (pin "1") (pinfunction "1_1") (pintype "unspecified"))
      (node (ref "U4") (pin "10") (pinfunction "P5_10") (pintype "unspecified"))
    )
    (net (code "22") (name "DISP_CLK") (class "Default")
      (node (ref "J2") (pin "3") (pinfunction "CLK_3") (pintype "unspecified"))
      (node (ref "R28") (pin "2") (pinfunction "2_2") (pintype "unspecified"))
      (node (ref "R30") (pin "2") (pinfunction "2_2") (pintype "unspecified"))
    )
    (net (code "23") (name "DISP_CS") (class "Default")
      (node (ref "J2") (pin "5") (pinfunction "CS_5") (pintype "unspecified"))
      (node (ref "R13") (pin "2") (pinfunction "2_2") (pintype "unspecified"))
      (node (ref "U2") (pin "28") (pinfunction "GPIO21_28") (pintype "unspecified"))
    )
    (net (code "24") (name "DISP_DATA") (class "Default")
      (node (ref "J2") (pin "4") (pinfunction "DATA_4") (pintype "unspecified"))
      (node (ref "R29") (pin "2") (pinfunction "2_2") (pintype "unspecified"))
      (node (ref "R31") (pin "2") (pinfunction "2_2") (pintype "unspecified"))
    )
    (net (code "25") (name "DISP_DC") (class "Default")
      (node (ref "J2") (pin "6") (pinfunction "DC_6") (pintype "unspecified"))
      (node (ref "R26") (pin "1") (pinfunction "1_1") (pintype "unspecified"))
      (node (ref "U4") (pin "7") (pinfunction "P3_7") (pintype "unspecified"))
    )
    (net (code "26") (name "DISP_RST_N") (class "Default")
      (node (ref "J2") (pin "7") (pinfunction "RST_7") (pintype "unspecified"))
      (node (ref "R25") (pin "1") (pinfunction "1_1") (pintype "unspecified"))
      (node (ref "U4") (pin "9") (pinfunction "P4_9") (pintype "unspecified"))
    )
    (net (code "27") (name "GND") (class "Default")
      (node (ref "ANT1") (pin "2") (pinfunction "SHORT_GND_2") (pintype "unspecified"))
      (node (ref "BT1") (pin "2") (pinfunction "-_2") (pintype "unspecified"))
      (node (ref "C1") (pin "2") (pinfunction "2_2") (pintype "unspecified"))
      (node (ref "C10") (pin "2") (pinfunction "2_2") (pintype "unspecified"))
      (node (ref "C11") (pin "2") (pinfunction "2_2") (pintype "unspecified"))
      (node (ref "C12") (pin "2") (pinfunction "2_2") (pintype "unspecified"))
      (node (ref "C13") (pin "2") (pinfunction "2_2") (pintype "unspecified"))
      (node (ref "C14") (pin "2") (pinfunction "2_2") (pintype "unspecified"))
      (node (ref "C15") (pin "2") (pinfunction "2_2") (pintype "unspecified"))
      (node (ref "C16") (pin "2") (pinfunction "2_2") (pintype "unspecified"))
      (node (ref "C17") (pin "2") (pinfunction "2_2") (pintype "unspecified"))
      (node (ref "C18") (pin "2") (pinfunction "2_2") (pintype "unspecified"))
      (node (ref "C19") (pin "2") (pinfunction "2_2") (pintype "unspecified"))
      (node (ref "C2") (pin "2") (pinfunction "2_2") (pintype "unspecified"))
      (node (ref "C20") (pin "2") (pinfunction "2_2") (pintype "unspecified"))
      (node (ref "C21") (pin "2") (pinfunction "2_2") (pintype "unspecified"))
      (node (ref "C22") (pin "2") (pinfunction "2_2") (pintype "unspecified"))
      (node (ref "C23") (pin "2") (pinfunction "2_2") (pintype "unspecified"))
      (node (ref "C24") (pin "2") (pinfunction "2_2") (pintype "unspecified"))
      (node (ref "C3") (pin "2") (pinfunction "2_2") (pintype "unspecified"))
      (node (ref "C4") (pin "2") (pinfunction "2_2") (pintype "unspecified"))
      (node (ref "C5") (pin "2") (pinfunction "2_2") (pintype "unspecified"))
      (node (ref "C6") (pin "2") (pinfunction "2_2") (pintype "unspecified"))
      (node (ref "C7") (pin "2") (pinfunction "2_2") (pintype "unspecified"))
      (node (ref "C8") (pin "2") (pinfunction "2_2") (pintype "unspecified"))
      (node (ref "C9") (pin "2") (pinfunction "2_2") (pintype "unspecified"))
      (node (ref "D2") (pin "3") (pinfunction "GND_3") (pintype "unspecified"))
      (node (ref "D3") (pin "3") (pinfunction "GND_3") (pintype "unspecified"))
      (node (ref "J1") (pin "2") (pinfunction "GND_2") (pintype "unspecified"))
      (node (ref "J1") (pin "3") (pinfunction "GND_3") (pintype "unspecified"))
      (node (ref "J2") (pin "2") (pinfunction "GND_2") (pintype "unspecified"))
      (node (ref "J3") (pin "2") (pinfunction "GND_2") (pintype "unspecified"))
      (node (ref "J4") (pin "1") (pinfunction "GND_1") (pintype "unspecified"))
      (node (ref "Q1") (pin "1") (pinfunction "G_1") (pintype "unspecified"))
      (node (ref "Q3") (pin "2") (pinfunction "S_2") (pintype "unspecified"))
      (node (ref "R16") (pin "2") (pinfunction "2_2") (pintype "unspecified"))
      (node (ref "R17") (pin "2") (pinfunction "2_2") (pintype "unspecified"))
      (node (ref "R2") (pin "2") (pinfunction "2_2") (pintype "unspecified"))
      (node (ref "R23") (pin "2") (pinfunction "2_2") (pintype "unspecified"))
      (node (ref "R25") (pin "2") (pinfunction "2_2") (pintype "unspecified"))
      (node (ref "R26") (pin "2") (pinfunction "2_2") (pintype "unspecified"))
      (node (ref "R27") (pin "2") (pinfunction "2_2") (pintype "unspecified"))
      (node (ref "R4") (pin "2") (pinfunction "2_2") (pintype "unspecified"))
      (node (ref "R7") (pin "2") (pinfunction "2_2") (pintype "unspecified"))
      (node (ref "RJ1") (pin "2") (pinfunction "GND_2") (pintype "unspecified"))
      (node (ref "RJ2") (pin "2") (pinfunction "GND_2") (pintype "unspecified"))
      (node (ref "SW2") (pin "2") (pinfunction "GND_2") (pintype "unspecified"))
      (node (ref "SW3") (pin "2") (pinfunction "GND_2") (pintype "unspecified"))
      (node (ref "TP1") (pin "1") (pinfunction "GND_1") (pintype "unspecified"))
      (node (ref "U1") (pin "2") (pinfunction "MODE_2") (pintype "unspecified"))
      (node (ref "U1") (pin "3") (pinfunction "AGND_3") (pintype "unspecified"))
      (node (ref "U1") (pin "8") (pinfunction "PGND_8") (pintype "unspecified"))
      (node (ref "U2") (pin "33") (pinfunction "EP_GND_33") (pintype "unspecified"))
      (node (ref "U3") (pin "1") (pinfunction "GND_1") (pintype "unspecified"))
      (node (ref "U3") (pin "10") (pinfunction "GND_10") (pintype "unspecified"))
      (node (ref "U3") (pin "11") (pinfunction "GND_11") (pintype "unspecified"))
      (node (ref "U3") (pin "12") (pinfunction "GND_12") (pintype "unspecified"))
      (node (ref "U3") (pin "2") (pinfunction "GND_2") (pintype "unspecified"))
      (node (ref "U3") (pin "20") (pinfunction "GND_20") (pintype "unspecified"))
      (node (ref "U3") (pin "22") (pinfunction "GND_22") (pintype "unspecified"))
      (node (ref "U3") (pin "3") (pinfunction "GND_3") (pintype "unspecified"))
      (node (ref "U3") (pin "4") (pinfunction "GND_4") (pintype "unspecified"))
      (node (ref "U3") (pin "5") (pinfunction "GND_5") (pintype "unspecified"))
      (node (ref "U4") (pin "1") (pinfunction "A0_1") (pintype "unspecified"))
      (node (ref "U4") (pin "2") (pinfunction "A1_2") (pintype "unspecified"))
      (node (ref "U4") (pin "3") (pinfunction "A2_3") (pintype "unspecified"))
      (node (ref "U4") (pin "8") (pinfunction "GND_8") (pintype "unspecified"))
      (node (ref "U5") (pin "2") (pinfunction "GND_2") (pintype "unspecified"))
      (node (ref "U5") (pin "8") (pinfunction "S_8") (pintype "unspecified"))
      (node (ref "U6") (pin "2") (pinfunction "GND_2") (pintype "unspecified"))
      (node (ref "U7") (pin "2") (pinfunction "GND_2") (pintype "unspecified"))
      (node (ref "U8") (pin "2") (pinfunction "GND_2") (pintype "unspecified"))
      (node (ref "Y1") (pin "2") (pinfunction "GND_2") (pintype "unspecified"))
      (node (ref "Y1") (pin "4") (pinfunction "GND_4") (pintype "unspecified"))
    )
    (net (code "28") (name "I2C_INT_SCL") (class "Default")
      (node (ref "J3") (pin "4") (pinfunction "SCL_4") (pintype "unspecified"))
      (node (ref "R12") (pin "2") (pinfunction "2_2") (pintype "unspecified"))
      (node (ref "R30") (pin "1") (pinfunction "1_1") (pintype "unspecified"))
      (node (ref "U2") (pin "14") (pinfunction "GPIO8_14") (pintype "unspecified"))
      (node (ref "U4") (pin "14") (pinfunction "SCL_14") (pintype "unspecified"))
    )
    (net (code "29") (name "I2C_INT_SDA") (class "Default")
      (node (ref "J3") (pin "3") (pinfunction "SDA_3") (pintype "unspecified"))
      (node (ref "R11") (pin "2") (pinfunction "2_2") (pintype "unspecified"))
      (node (ref "R31") (pin "1") (pinfunction "1_1") (pintype "unspecified"))
      (node (ref "U2") (pin "16") (pinfunction "GPIO10_16") (pintype "unspecified"))
      (node (ref "U4") (pin "15") (pinfunction "SDA_15") (pintype "unspecified"))
    )
    (net (code "30") (name "LED_A") (class "Default")
      (node (ref "D1") (pin "1") (pinfunction "A_1") (pintype "unspecified"))
      (node (ref "R21") (pin "2") (pinfunction "2_2") (pintype "unspecified"))
    )
    (net (code "31") (name "LED_N") (class "Default")
      (node (ref "D1") (pin "2") (pinfunction "K_2") (pintype "unspecified"))
      (node (ref "R22") (pin "2") (pinfunction "2_2") (pintype "unspecified"))
      (node (ref "U4") (pin "6") (pinfunction "P2_6") (pintype "unspecified"))
    )
    (net (code "32") (name "LORA_ANT") (class "Default")
      (node (ref "J1") (pin "1") (pinfunction "RF_1") (pintype "unspecified"))
      (node (ref "U3") (pin "21") (pinfunction "ANT_21") (pintype "unspecified"))
    )
    (net (code "33") (name "LORA_BUSY") (class "Default")
      (node (ref "TP6") (pin "1") (pinfunction "LORA_BUSY_1") (pintype "unspecified"))
      (node (ref "U2") (pin "9") (pinfunction "GPIO4_9") (pintype "unspecified"))
      (node (ref "U3") (pin "14") (pinfunction "BUSY_14") (pintype "unspecified"))
    )
    (net (code "34") (name "LORA_DIO1") (class "Default")
      (node (ref "U2") (pin "8") (pinfunction "GPIO3_8") (pintype "unspecified"))
      (node (ref "U3") (pin "13") (pinfunction "DIO1_13") (pintype "unspecified"))
    )
    (net (code "35") (name "LORA_DIO2") (class "Default")
      (node (ref "R15") (pin "1") (pinfunction "1_1") (pintype "unspecified"))
      (node (ref "U3") (pin "8") (pinfunction "DIO2_8") (pintype "unspecified"))
    )
    (net (code "36") (name "LORA_MOSI") (class "Default")
      (node (ref "R20") (pin "2") (pinfunction "2_2") (pintype "unspecified"))
      (node (ref "U3") (pin "17") (pinfunction "MOSI_17") (pintype "unspecified"))
    )
    (net (code "37") (name "LORA_NSS") (class "Default")
      (node (ref "R10") (pin "2") (pinfunction "2_2") (pintype "unspecified"))
      (node (ref "U2") (pin "6") (pinfunction "GPIO2_6") (pintype "unspecified"))
      (node (ref "U3") (pin "19") (pinfunction "NSS_19") (pintype "unspecified"))
    )
    (net (code "38") (name "LORA_RST_N") (class "Default")
      (node (ref "R18") (pin "2") (pinfunction "2_2") (pintype "unspecified"))
      (node (ref "U3") (pin "15") (pinfunction "NRST_15") (pintype "unspecified"))
      (node (ref "U4") (pin "4") (pinfunction "P0_4") (pintype "unspecified"))
    )
    (net (code "39") (name "LORA_RXEN") (class "Default")
      (node (ref "R17") (pin "1") (pinfunction "1_1") (pintype "unspecified"))
      (node (ref "U3") (pin "6") (pinfunction "RXEN_6") (pintype "unspecified"))
      (node (ref "U4") (pin "5") (pinfunction "P1_5") (pintype "unspecified"))
    )
    (net (code "40") (name "LORA_SCK") (class "Default")
      (node (ref "R19") (pin "2") (pinfunction "2_2") (pintype "unspecified"))
      (node (ref "U3") (pin "18") (pinfunction "SCK_18") (pintype "unspecified"))
    )
    (net (code "41") (name "LORA_TXEN") (class "Default")
      (node (ref "R15") (pin "2") (pinfunction "2_2") (pintype "unspecified"))
      (node (ref "R16") (pin "1") (pinfunction "1_1") (pintype "unspecified"))
      (node (ref "U3") (pin "7") (pinfunction "TXEN_7") (pintype "unspecified"))
    )
    (net (code "42") (name "PORT_A_IO") (class "Default")
      (node (ref "R33") (pin "1") (pinfunction "1_1") (pintype "unspecified"))
      (node (ref "R37") (pin "1") (pinfunction "1_1") (pintype "unspecified"))
      (node (ref "U2") (pin "5") (pinfunction "GPIO1_5") (pintype "unspecified"))
    )
    (net (code "43") (name "PORT_B_IO") (class "Default")
      (node (ref "R34") (pin "1") (pinfunction "1_1") (pintype "unspecified"))
      (node (ref "R38") (pin "2") (pinfunction "2_2") (pintype "unspecified"))
      (node (ref "U2") (pin "27") (pinfunction "GPIO20_27") (pintype "unspecified"))
    )
    (net (code "44") (name "PSU_EN") (class "Default")
      (node (ref "R3") (pin "2") (pinfunction "2_2") (pintype "unspecified"))
      (node (ref "R4") (pin "1") (pinfunction "1_1") (pintype "unspecified"))
      (node (ref "U1") (pin "1") (pinfunction "EN_1") (pintype "unspecified"))
    )
    (net (code "45") (name "PSU_FB") (class "Default")
      (node (ref "R1") (pin "2") (pinfunction "2_2") (pintype "unspecified"))
      (node (ref "R2") (pin "1") (pinfunction "1_1") (pintype "unspecified"))
      (node (ref "U1") (pin "4") (pinfunction "FB_4") (pintype "unspecified"))
    )
    (net (code "46") (name "PSU_PG") (class "Default")
      (node (ref "R5") (pin "2") (pinfunction "2_2") (pintype "unspecified"))
      (node (ref "TP5") (pin "1") (pinfunction "PSU_PG_1") (pintype "unspecified"))
      (node (ref "U1") (pin "5") (pinfunction "PG_5") (pintype "unspecified"))
    )
    (net (code "47") (name "SENS_EN") (class "Default")
      (node (ref "Q3") (pin "1") (pinfunction "G_1") (pintype "unspecified"))
      (node (ref "R23") (pin "1") (pinfunction "1_1") (pintype "unspecified"))
      (node (ref "U4") (pin "11") (pinfunction "P6_11") (pintype "unspecified"))
    )
    (net (code "48") (name "SENS_GATE") (class "Default")
      (node (ref "Q2") (pin "1") (pinfunction "G_1") (pintype "unspecified"))
      (node (ref "Q3") (pin "3") (pinfunction "D_3") (pintype "unspecified"))
      (node (ref "R32") (pin "2") (pinfunction "2_2") (pintype "unspecified"))
    )
    (net (code "49") (name "SENS_PRE") (class "Default")
      (node (ref "F2") (pin "1") (pinfunction "1_1") (pintype "unspecified"))
      (node (ref "Q2") (pin "3") (pinfunction "D_3") (pintype "unspecified"))
    )
    (net (code "50") (name "SPI_MISO") (class "Default")
      (node (ref "U2") (pin "10") (pinfunction "GPIO5_10") (pintype "unspecified"))
      (node (ref "U3") (pin "16") (pinfunction "MISO_16") (pintype "unspecified"))
    )
    (net (code "51") (name "SPI_MOSI") (class "Default")
      (node (ref "R20") (pin "1") (pinfunction "1_1") (pintype "unspecified"))
      (node (ref "R29") (pin "1") (pinfunction "1_1") (pintype "unspecified"))
      (node (ref "U2") (pin "13") (pinfunction "GPIO7_13") (pintype "unspecified"))
    )
    (net (code "52") (name "SPI_SCK") (class "Default")
      (node (ref "R19") (pin "1") (pinfunction "1_1") (pintype "unspecified"))
      (node (ref "R28") (pin "1") (pinfunction "1_1") (pintype "unspecified"))
      (node (ref "U2") (pin "12") (pinfunction "GPIO6_12") (pintype "unspecified"))
    )
    (net (code "53") (name "SW_L1") (class "Default")
      (node (ref "L1") (pin "1") (pinfunction "1_1") (pintype "unspecified"))
      (node (ref "U1") (pin "9") (pinfunction "L1_9") (pintype "unspecified"))
    )
    (net (code "54") (name "SW_L2") (class "Default")
      (node (ref "L1") (pin "2") (pinfunction "2_2") (pintype "unspecified"))
      (node (ref "U1") (pin "7") (pinfunction "L2_7") (pintype "unspecified"))
    )
    (net (code "55") (name "USB_DM") (class "Default")
      (node (ref "J4") (pin "2") (pinfunction "D-_2") (pintype "unspecified"))
      (node (ref "R43") (pin "2") (pinfunction "2_2") (pintype "unspecified"))
      (node (ref "U8") (pin "1") (pinfunction "IO1_1") (pintype "unspecified"))
      (node (ref "U8") (pin "6") (pinfunction "IO1_6") (pintype "unspecified"))
    )
    (net (code "56") (name "USB_DM_MCU") (class "Default")
      (node (ref "R43") (pin "1") (pinfunction "1_1") (pintype "unspecified"))
      (node (ref "U2") (pin "25") (pinfunction "GPIO18_USB_DM_25") (pintype "unspecified"))
    )
    (net (code "57") (name "USB_DP") (class "Default")
      (node (ref "J4") (pin "3") (pinfunction "D+_3") (pintype "unspecified"))
      (node (ref "R44") (pin "2") (pinfunction "2_2") (pintype "unspecified"))
      (node (ref "U8") (pin "3") (pinfunction "IO2_3") (pintype "unspecified"))
      (node (ref "U8") (pin "4") (pinfunction "IO2_4") (pintype "unspecified"))
    )
    (net (code "58") (name "USB_DP_MCU") (class "Default")
      (node (ref "R44") (pin "1") (pinfunction "1_1") (pintype "unspecified"))
      (node (ref "U2") (pin "26") (pinfunction "GPIO19_USB_DP_26") (pintype "unspecified"))
    )
    (net (code "59") (name "VDD_SPI") (class "Default")
      (node (ref "C10") (pin "1") (pinfunction "1_1") (pintype "unspecified"))
      (node (ref "U2") (pin "18") (pinfunction "VDD_SPI_18") (pintype "unspecified"))
    )
    (net (code "60") (name "VEXT") (class "Default")
      (node (ref "C23") (pin "1") (pinfunction "1_1") (pintype "unspecified"))
      (node (ref "F2") (pin "2") (pinfunction "2_2") (pintype "unspecified"))
      (node (ref "R35") (pin "1") (pinfunction "1_1") (pintype "unspecified"))
      (node (ref "R36") (pin "1") (pinfunction "1_1") (pintype "unspecified"))
      (node (ref "RJ1") (pin "1") (pinfunction "VCC_1") (pintype "unspecified"))
      (node (ref "RJ2") (pin "1") (pinfunction "VCC_1") (pintype "unspecified"))
      (node (ref "U6") (pin "5") (pinfunction "VBUS_5") (pintype "unspecified"))
      (node (ref "U7") (pin "5") (pinfunction "VBUS_5") (pintype "unspecified"))
    )
    (net (code "61") (name "XTAL_N") (class "Default")
      (node (ref "C15") (pin "1") (pinfunction "1_1") (pintype "unspecified"))
      (node (ref "U2") (pin "29") (pinfunction "XTAL_N_29") (pintype "unspecified"))
      (node (ref "Y1") (pin "3") (pinfunction "X2_3") (pintype "unspecified"))
    )
    (net (code "62") (name "XTAL_P") (class "Default")
      (node (ref "C14") (pin "1") (pinfunction "1_1") (pintype "unspecified"))
      (node (ref "U2") (pin "30") (pinfunction "XTAL_P_30") (pintype "unspecified"))
      (node (ref "Y1") (pin "1") (pinfunction "X1_1") (pintype "unspecified"))
    )
    (net (code "63") (name "unconnected-(J4-NC_5V_PROIBIDO-Pad4)") (class "Default")
      (node (ref "J4") (pin "4") (pinfunction "NC_5V_PROIBIDO_4") (pintype "unspecified+no_connect"))
    )
    (net (code "64") (name "unconnected-(U2-SPICLK_FLASH-Pad22)") (class "Default")
      (node (ref "U2") (pin "22") (pinfunction "SPICLK_FLASH_22") (pintype "unspecified+no_connect"))
    )
    (net (code "65") (name "unconnected-(U2-SPICS0_FLASH-Pad21)") (class "Default")
      (node (ref "U2") (pin "21") (pinfunction "SPICS0_FLASH_21") (pintype "unspecified+no_connect"))
    )
    (net (code "66") (name "unconnected-(U2-SPID_FLASH-Pad23)") (class "Default")
      (node (ref "U2") (pin "23") (pinfunction "SPID_FLASH_23") (pintype "unspecified+no_connect"))
    )
    (net (code "67") (name "unconnected-(U2-SPIHD_FLASH-Pad19)") (class "Default")
      (node (ref "U2") (pin "19") (pinfunction "SPIHD_FLASH_19") (pintype "unspecified+no_connect"))
    )
    (net (code "68") (name "unconnected-(U2-SPIQ_FLASH-Pad24)") (class "Default")
      (node (ref "U2") (pin "24") (pinfunction "SPIQ_FLASH_24") (pintype "unspecified+no_connect"))
    )
    (net (code "69") (name "unconnected-(U2-SPIWP_FLASH-Pad20)") (class "Default")
      (node (ref "U2") (pin "20") (pinfunction "SPIWP_FLASH_20") (pintype "unspecified+no_connect"))
    )
    (net (code "70") (name "unconnected-(U4-INT-Pad13)") (class "Default")
      (node (ref "U4") (pin "13") (pinfunction "INT_13") (pintype "unspecified+no_connect"))
    )
  )
)
